# 01-Microcontroller.net
KiCad netlist of a schematic drawn in Altium Designer
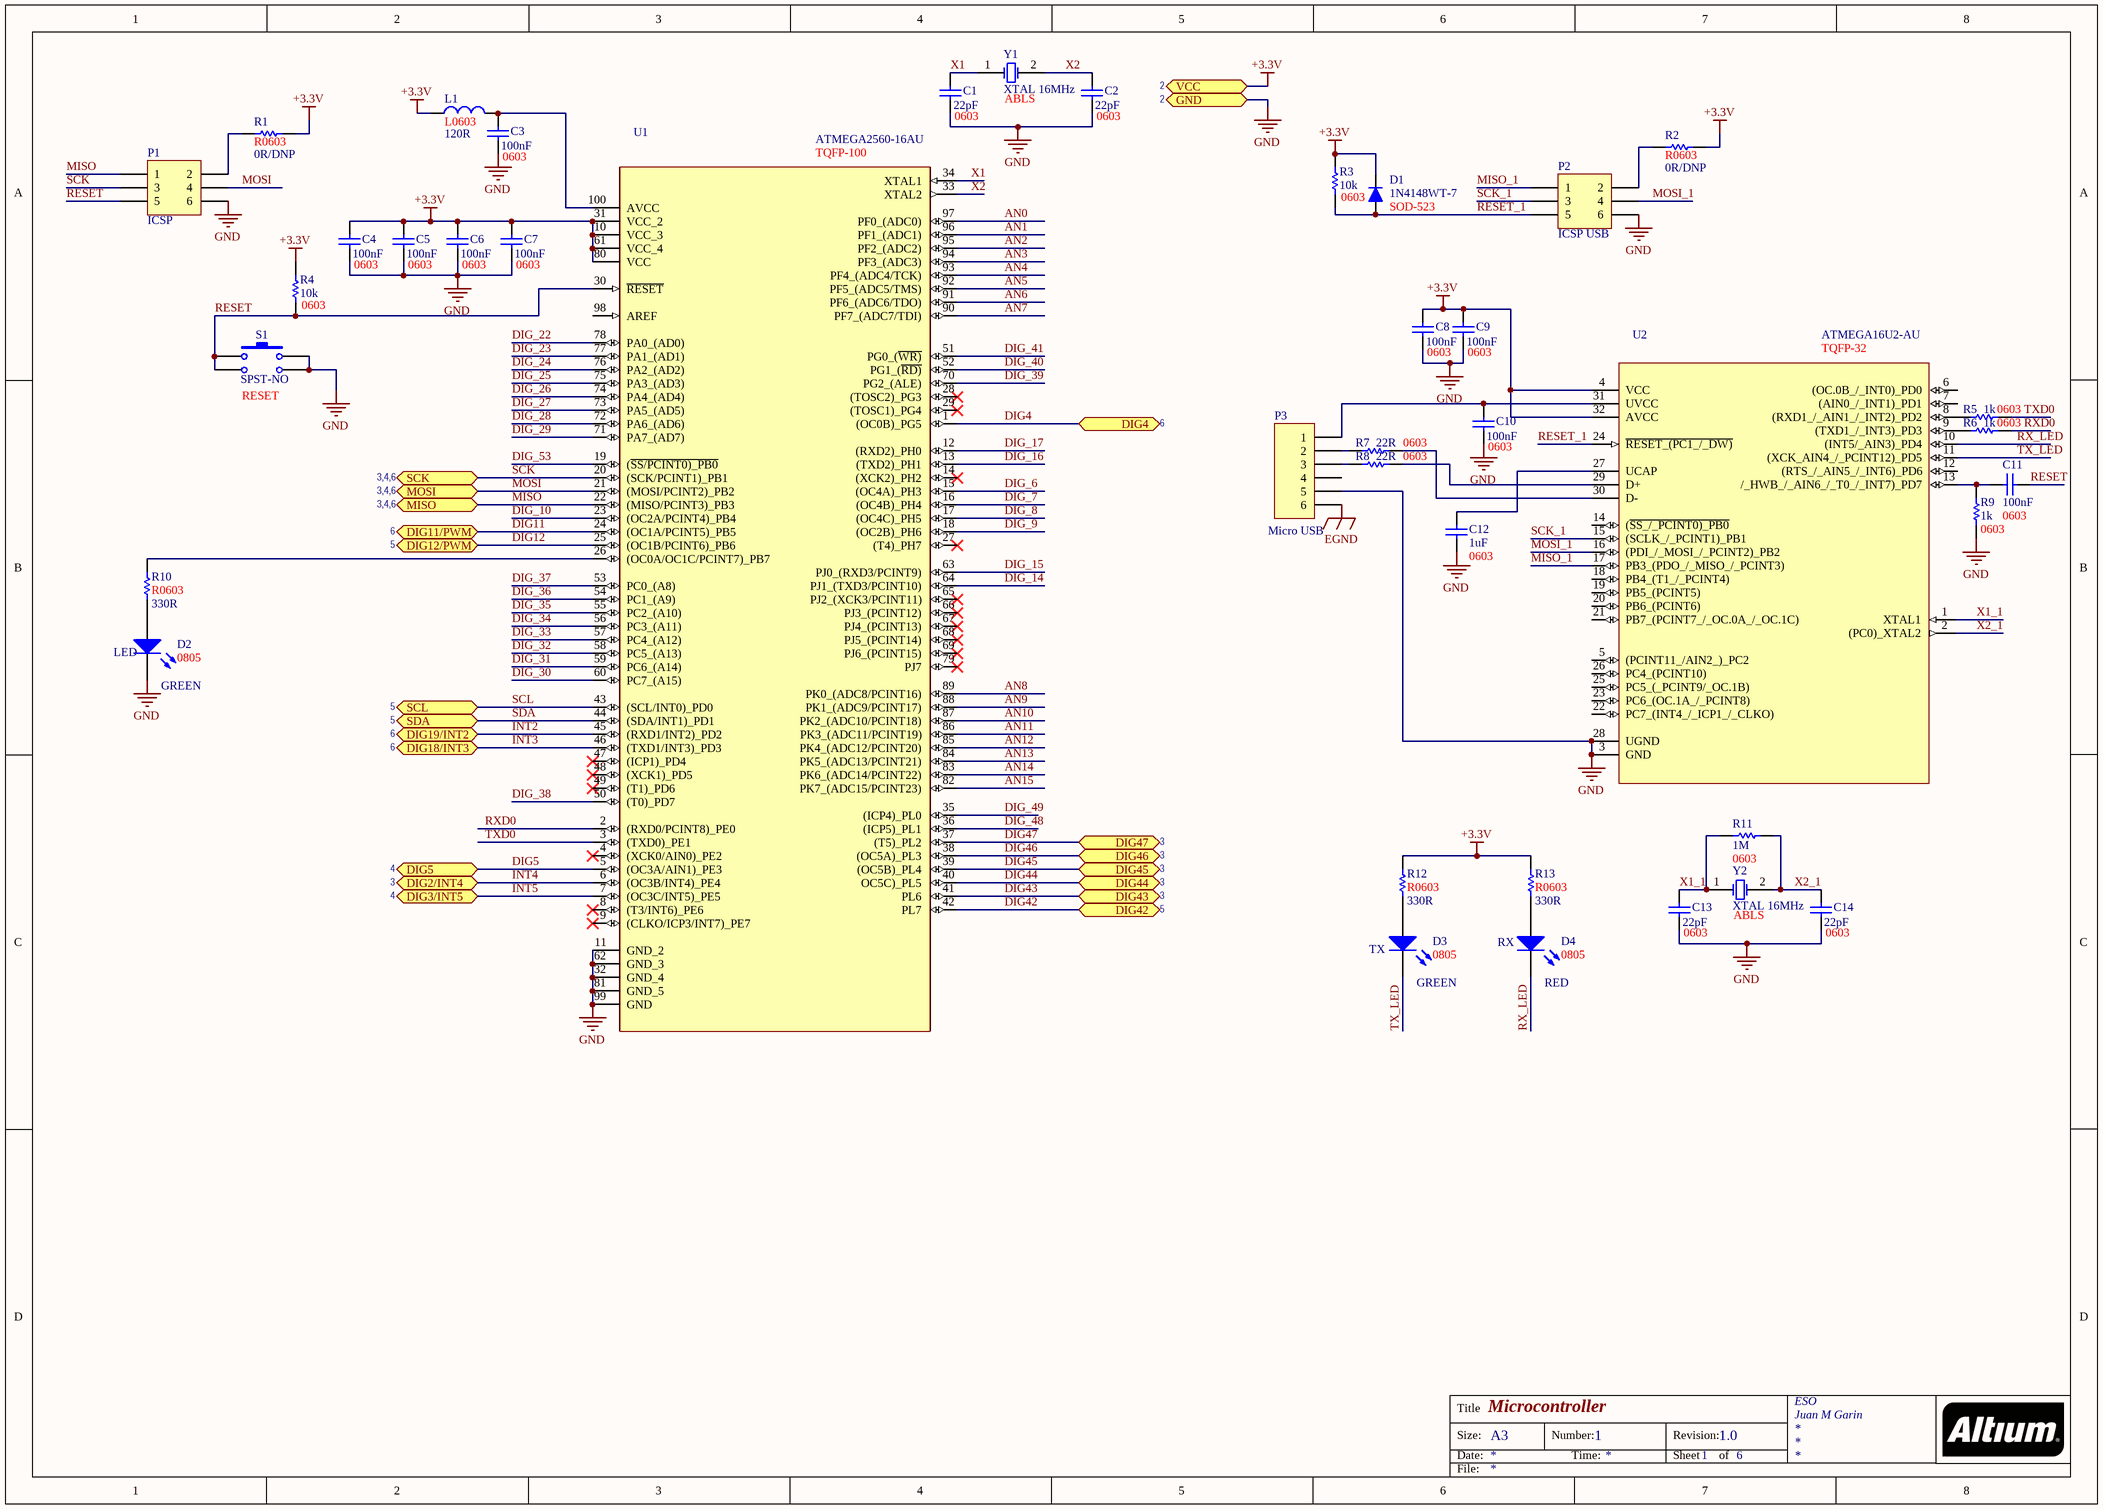
[diagram p0: 01-Microcontroller.SchDoc]

(export (version "E")
  (design (tool "Eeschema 10.0.6"))
  (components
    (comp (ref "C1")
      (value "22pF")
      (footprint "C0603")
      (description "Capacitor (Semiconductor SIM Model)")
      (fields
        (field (name "MANUFACTURER PART NUMBER") "885012006004")
        (field (name "PACKAGEREFERENCE") "0603")
      )
      (libsource (lib "Miscellaneous Devices") (part "Cap Semi"))
    )
    (comp (ref "C2")
      (value "22pF")
      (footprint "C0603")
      (description "Capacitor (Semiconductor SIM Model)")
      (fields
        (field (name "MANUFACTURER PART NUMBER") "885012006004")
        (field (name "PACKAGEREFERENCE") "0603")
      )
      (libsource (lib "Miscellaneous Devices") (part "Cap Semi"))
    )
    (comp (ref "C3")
      (value "100nF")
      (footprint "C0603")
      (description "Capacitor (Semiconductor SIM Model)")
      (fields
        (field (name "MANUFACTURER PART NUMBER") "CL10F104ZO8NNNC")
        (field (name "PACKAGEREFERENCE") "0603")
      )
      (libsource (lib "Miscellaneous Devices") (part "Cap Semi"))
    )
    (comp (ref "C4")
      (value "100nF")
      (footprint "C0603")
      (description "Capacitor (Semiconductor SIM Model)")
      (fields
        (field (name "MANUFACTURER PART NUMBER") "CL10F104ZO8NNNC")
        (field (name "PACKAGEREFERENCE") "0603")
      )
      (libsource (lib "Miscellaneous Devices") (part "Cap Semi"))
    )
    (comp (ref "C5")
      (value "100nF")
      (footprint "C0603")
      (description "Capacitor (Semiconductor SIM Model)")
      (fields
        (field (name "MANUFACTURER PART NUMBER") "CL10F104ZO8NNNC")
        (field (name "PACKAGEREFERENCE") "0603")
      )
      (libsource (lib "Miscellaneous Devices") (part "Cap Semi"))
    )
    (comp (ref "C6")
      (value "100nF")
      (footprint "C0603")
      (description "Capacitor (Semiconductor SIM Model)")
      (fields
        (field (name "MANUFACTURER PART NUMBER") "CL10F104ZO8NNNC")
        (field (name "PACKAGEREFERENCE") "0603")
      )
      (libsource (lib "Miscellaneous Devices") (part "Cap Semi"))
    )
    (comp (ref "C7")
      (value "100nF")
      (footprint "C0603")
      (description "Capacitor (Semiconductor SIM Model)")
      (fields
        (field (name "MANUFACTURER PART NUMBER") "CL10F104ZO8NNNC")
        (field (name "PACKAGEREFERENCE") "0603")
      )
      (libsource (lib "Miscellaneous Devices") (part "Cap Semi"))
    )
    (comp (ref "C8")
      (value "100nF")
      (footprint "C0603")
      (description "Capacitor (Semiconductor SIM Model)")
      (fields
        (field (name "MANUFACTURER PART NUMBER") "CL10F104ZO8NNNC")
        (field (name "PACKAGEREFERENCE") "0603")
      )
      (libsource (lib "Miscellaneous Devices") (part "Cap Semi"))
    )
    (comp (ref "C9")
      (value "100nF")
      (footprint "C0603")
      (description "Capacitor (Semiconductor SIM Model)")
      (fields
        (field (name "MANUFACTURER PART NUMBER") "CL10F104ZO8NNNC")
        (field (name "PACKAGEREFERENCE") "0603")
      )
      (libsource (lib "Miscellaneous Devices") (part "Cap Semi"))
    )
    (comp (ref "C10")
      (value "100nF")
      (footprint "C0603")
      (description "Capacitor (Semiconductor SIM Model)")
      (fields
        (field (name "MANUFACTURER PART NUMBER") "CL10F104ZO8NNNC")
        (field (name "PACKAGEREFERENCE") "0603")
      )
      (libsource (lib "Miscellaneous Devices") (part "Cap Semi"))
    )
    (comp (ref "C11")
      (value "100nF")
      (footprint "C0603")
      (description "Capacitor (Semiconductor SIM Model)")
      (fields
        (field (name "MANUFACTURER PART NUMBER") "CL10F104ZO8NNNC")
        (field (name "PACKAGEREFERENCE") "0603")
      )
      (libsource (lib "Miscellaneous Devices") (part "Cap Semi"))
    )
    (comp (ref "C12")
      (value "1uF")
      (footprint "C0603")
      (description "Capacitor (Semiconductor SIM Model)")
      (fields
        (field (name "MANUFACTURER PART NUMBER") "CL10A105KQ8NNNC")
        (field (name "PACKAGEREFERENCE") "0603")
      )
      (libsource (lib "Miscellaneous Devices") (part "Cap Semi"))
    )
    (comp (ref "C13")
      (value "22pF")
      (footprint "C0603")
      (description "Capacitor (Semiconductor SIM Model)")
      (fields
        (field (name "MANUFACTURER PART NUMBER") "885012006004")
        (field (name "PACKAGEREFERENCE") "0603")
      )
      (libsource (lib "Miscellaneous Devices") (part "Cap Semi"))
    )
    (comp (ref "C14")
      (value "22pF")
      (footprint "C0603")
      (description "Capacitor (Semiconductor SIM Model)")
      (fields
        (field (name "MANUFACTURER PART NUMBER") "885012006004")
        (field (name "PACKAGEREFERENCE") "0603")
      )
      (libsource (lib "Miscellaneous Devices") (part "Cap Semi"))
    )
    (comp (ref "D1")
      (value "1N4148WT-7")
      (footprint "SOD523")
      (description "Diode")
      (fields (field (name "PACKAGEREFERENCE") "SOD-523"))
      (libsource (lib "schematic_library") (part "DIODE"))
    )
    (comp (ref "D2")
      (value "LED")
      (footprint "LED0805")
      (description "GREEN")
      (fields
        (field (name "PACKAGEREFERENCE") "0805")
        (field (name "ALTIUM_VALUE") "GREEN")
        (field (name "MANUFACTURER PART NUMBER") "LTST-S220GKT")
      )
      (libsource (lib "Library_Scott") (part "LED_SMD"))
    )
    (comp (ref "D3")
      (value "TX")
      (footprint "LED0805")
      (description "GREEN")
      (fields
        (field (name "PACKAGEREFERENCE") "0805")
        (field (name "ALTIUM_VALUE") "GREEN")
        (field (name "MANUFACTURER PART NUMBER") "LTST-S220GKT")
      )
      (libsource (lib "Library_Scott") (part "LED_SMD"))
    )
    (comp (ref "D4")
      (value "RX")
      (footprint "LED0805")
      (description "YLW")
      (fields
        (field (name "PACKAGEREFERENCE") "0805")
        (field (name "ALTIUM_VALUE") "RED")
        (field (name "MANUFACTURER PART NUMBER") "LTST-C171KRKT")
      )
      (libsource (lib "Library_Scott") (part "LED_SMD"))
    )
    (comp (ref "L1")
      (value "120R")
      (footprint "L0603")
      (description "Inductor")
      (fields
        (field (name "MANUFACTURER PART NUMBER") "BLM18PG121SN1D")
        (field (name "PACKAGEREFERENCE") "L0603")
      )
      (libsource (lib "schematic_library") (part "Inductor_0603"))
    )
    (comp (ref "P1")
      (value "ICSP")
      (footprint "HDR2X3")
      (description "Header, 3-Pin, Dual row")
      (fields (field (name "MANUFACTURER PART NUMBER") "5-146254-3"))
      (libsource (lib "Library_Scott") (part "Header 3X2"))
    )
    (comp (ref "P2")
      (value "ICSP USB")
      (footprint "HDR2X3")
      (description "Header, 3-Pin, Dual row")
      (fields (field (name "MANUFACTURER PART NUMBER") "5-146254-3"))
      (libsource (lib "Library_Scott") (part "Header 3X2"))
    )
    (comp (ref "P3")
      (value "Micro USB")
      (footprint "CON_MOLEX_105133-0011")
      (description "CONN MICRO USB B 2.0 VERT SMT")
      (fields (field (name "MANUFACTURER PART NUMBER") "1051330011"))
      (libsource (lib "Miscellaneous Connectors") (part "Header 6"))
    )
    (comp (ref "R1")
      (value "0R/DNP")
      (footprint "R0603")
      (description "Resistor")
      (fields
        (field (name "MANUFACTURER PART NUMBER") "CR0603-J/-000ELF")
        (field (name "PACKAGEREFERENCE") "R0603")
      )
      (libsource (lib "schematic_library") (part "Res_0402"))
    )
    (comp (ref "R2")
      (value "0R/DNP")
      (footprint "R0603")
      (description "Resistor")
      (fields
        (field (name "MANUFACTURER PART NUMBER") "CR0603-J/-000ELF")
        (field (name "PACKAGEREFERENCE") "R0603")
      )
      (libsource (lib "schematic_library") (part "Res_0402"))
    )
    (comp (ref "R3")
      (value "10k")
      (footprint "R0603")
      (description "Resistor")
      (fields
        (field (name "MANUFACTURER PART NUMBER") "RMCF0603FT10K0")
        (field (name "PACKAGEREFERENCE") "0603")
      )
      (libsource (lib "Miscellaneous Devices") (part "Res1"))
    )
    (comp (ref "R4")
      (value "10k")
      (footprint "R0603")
      (description "Resistor")
      (fields
        (field (name "MANUFACTURER PART NUMBER") "RMCF0603FT10K0")
        (field (name "PACKAGEREFERENCE") "0603")
      )
      (libsource (lib "Miscellaneous Devices") (part "Res1"))
    )
    (comp (ref "R5")
      (value "1k")
      (footprint "R0603")
      (description "Resistor")
      (fields
        (field (name "MANUFACTURER PART NUMBER") "RMCF0603FG1K00")
        (field (name "PACKAGEREFERENCE") "0603")
      )
      (libsource (lib "Miscellaneous Devices") (part "Res1"))
    )
    (comp (ref "R6")
      (value "1k")
      (footprint "R0603")
      (description "Resistor")
      (fields
        (field (name "MANUFACTURER PART NUMBER") "RMCF0603FG1K00")
        (field (name "PACKAGEREFERENCE") "0603")
      )
      (libsource (lib "Miscellaneous Devices") (part "Res1"))
    )
    (comp (ref "R7")
      (value "22R")
      (footprint "R0603")
      (description "Resistor")
      (fields
        (field (name "MANUFACTURER PART NUMBER") "CRGCQ0603J22R")
        (field (name "PACKAGEREFERENCE") "0603")
      )
      (libsource (lib "Miscellaneous Devices") (part "Res1"))
    )
    (comp (ref "R8")
      (value "22R")
      (footprint "R0603")
      (description "Resistor")
      (fields
        (field (name "MANUFACTURER PART NUMBER") "CRGCQ0603J22R")
        (field (name "PACKAGEREFERENCE") "0603")
      )
      (libsource (lib "Miscellaneous Devices") (part "Res1"))
    )
    (comp (ref "R9")
      (value "1k")
      (footprint "R0603")
      (description "Resistor")
      (fields
        (field (name "MANUFACTURER PART NUMBER") "RMCF0603FG1K00")
        (field (name "PACKAGEREFERENCE") "0603")
      )
      (libsource (lib "Miscellaneous Devices") (part "Res1"))
    )
    (comp (ref "R10")
      (value "330R")
      (footprint "R0603")
      (description "Resistor")
      (fields
        (field (name "MANUFACTURER PART NUMBER") "RMCF0603JT330R")
        (field (name "PACKAGEREFERENCE") "R0603")
      )
      (libsource (lib "schematic_library") (part "Res_0402"))
    )
    (comp (ref "R11")
      (value "1M")
      (footprint "R0603")
      (description "Resistor")
      (fields
        (field (name "MANUFACTURER PART NUMBER") "RMCF0603FG1M00")
        (field (name "PACKAGEREFERENCE") "0603")
      )
      (libsource (lib "Miscellaneous Devices") (part "Res1"))
    )
    (comp (ref "R12")
      (value "330R")
      (footprint "R0603")
      (description "Resistor")
      (fields
        (field (name "MANUFACTURER PART NUMBER") "RMCF0603JT330R")
        (field (name "PACKAGEREFERENCE") "R0603")
      )
      (libsource (lib "schematic_library") (part "Res_0402"))
    )
    (comp (ref "R13")
      (value "330R")
      (footprint "R0603")
      (description "Resistor")
      (fields
        (field (name "MANUFACTURER PART NUMBER") "RMCF0603JT330R")
        (field (name "PACKAGEREFERENCE") "R0603")
      )
      (libsource (lib "schematic_library") (part "Res_0402"))
    )
    (comp (ref "S1")
      (value "SPST-NO")
      (footprint "DPST-4")
      (description "Switch")
      (fields
        (field (name "MANUFACTURER PART NUMBER") "PTS645SM43SMTR92 LFS")
        (field (name "FUNCTION") "RESET")
      )
      (libsource (lib "Library_Scott") (part "SW-PB"))
    )
    (comp (ref "U1")
      (value "ATMEGA2560-16AU")
      (footprint "TQFP100")
      (fields (field (name "PACKAGEREFERENCE") "TQFP-100"))
      (libsource (lib "Library") (part "ATMEGA2560-16AU"))
    )
    (comp (ref "U2")
      (value "ATMEGA16U2-AU")
      (footprint "32A_N")
      (description "MCU 8-bit ATmega AVR RISC 16KB Flash 3.3V/5V 32-Pin TQFP")
      (fields (field (name "PACKAGE") "TQFP-32"))
      (libsource (lib "Library") (part "ATMEGA16U2-AU"))
    )
    (comp (ref "Y1")
      (value "XTAL 16MHz")
      (footprint "XTAL-SMD")
      (description "Crystal Oscillator 16MHz SMD")
      (fields
        (field (name "MANUFACTURER PART NUMBER") "ABLS-16.000MHZ-B2-T")
        (field (name "PACKAGEREFERENCE") "ABLS")
      )
      (libsource (lib "Library_Scott") (part "XTAL 16MHz"))
    )
    (comp (ref "Y2")
      (value "XTAL 16MHz")
      (footprint "XTAL-SMD")
      (description "Crystal Oscillator 16MHz SMD")
      (fields
        (field (name "MANUFACTURER PART NUMBER") "ABLS-16.000MHZ-B2-T")
        (field (name "PACKAGEREFERENCE") "ABLS")
      )
      (libsource (lib "Library_Scott") (part "XTAL 16MHz"))
    )
  )
  (nets
    (net (code "1") (name "+3.3V") (class "Default")
      (node (ref "C4") (pin "2") (pinfunction "2_2") (pintype "passive"))
      (node (ref "C5") (pin "2") (pinfunction "2_2") (pintype "passive"))
      (node (ref "C6") (pin "2") (pinfunction "2_2") (pintype "passive"))
      (node (ref "C7") (pin "2") (pinfunction "2_2") (pintype "passive"))
      (node (ref "C8") (pin "2") (pinfunction "2_2") (pintype "passive"))
      (node (ref "C9") (pin "2") (pinfunction "2_2") (pintype "passive"))
      (node (ref "D1") (pin "2") (pinfunction "K_2") (pintype "passive"))
      (node (ref "L1") (pin "1") (pinfunction "1_1") (pintype "passive"))
      (node (ref "R1") (pin "2") (pinfunction "2_2") (pintype "passive"))
      (node (ref "R12") (pin "2") (pinfunction "2_2") (pintype "passive"))
      (node (ref "R13") (pin "2") (pinfunction "2_2") (pintype "passive"))
      (node (ref "R2") (pin "2") (pinfunction "2_2") (pintype "passive"))
      (node (ref "R3") (pin "1") (pinfunction "1_1") (pintype "passive"))
      (node (ref "R4") (pin "1") (pinfunction "1_1") (pintype "passive"))
      (node (ref "U1") (pin "10") (pinfunction "VCC_3_10") (pintype "power_in"))
      (node (ref "U1") (pin "31") (pinfunction "VCC_2_31") (pintype "power_in"))
      (node (ref "U1") (pin "61") (pinfunction "VCC_4_61") (pintype "power_in"))
      (node (ref "U1") (pin "80") (pinfunction "VCC_80") (pintype "power_in"))
      (node (ref "U2") (pin "32") (pinfunction "AVCC_32") (pintype "power_in"))
      (node (ref "U2") (pin "4") (pinfunction "VCC_4") (pintype "power_in"))
    )
    (net (code "2") (name "/AN0") (class "Default")
      (node (ref "U1") (pin "97") (pinfunction "PF0_(ADC0)_97") (pintype "bidirectional"))
    )
    (net (code "3") (name "/AN1") (class "Default")
      (node (ref "U1") (pin "96") (pinfunction "PF1_(ADC1)_96") (pintype "bidirectional"))
    )
    (net (code "4") (name "/AN2") (class "Default")
      (node (ref "U1") (pin "95") (pinfunction "PF2_(ADC2)_95") (pintype "bidirectional"))
    )
    (net (code "5") (name "/AN3") (class "Default")
      (node (ref "U1") (pin "94") (pinfunction "PF3_(ADC3)_94") (pintype "bidirectional"))
    )
    (net (code "6") (name "/AN4") (class "Default")
      (node (ref "U1") (pin "93") (pinfunction "PF4_(ADC4/TCK)_93") (pintype "bidirectional"))
    )
    (net (code "7") (name "/AN5") (class "Default")
      (node (ref "U1") (pin "92") (pinfunction "PF5_(ADC5/TMS)_92") (pintype "bidirectional"))
    )
    (net (code "8") (name "/AN6") (class "Default")
      (node (ref "U1") (pin "91") (pinfunction "PF6_(ADC6/TDO)_91") (pintype "bidirectional"))
    )
    (net (code "9") (name "/AN7") (class "Default")
      (node (ref "U1") (pin "90") (pinfunction "PF7_(ADC7/TDI)_90") (pintype "bidirectional"))
    )
    (net (code "10") (name "/AN8") (class "Default")
      (node (ref "U1") (pin "89") (pinfunction "PK0_(ADC8/PCINT16)_89") (pintype "bidirectional"))
    )
    (net (code "11") (name "/AN9") (class "Default")
      (node (ref "U1") (pin "88") (pinfunction "PK1_(ADC9/PCINT17)_88") (pintype "bidirectional"))
    )
    (net (code "12") (name "/AN10") (class "Default")
      (node (ref "U1") (pin "87") (pinfunction "PK2_(ADC10/PCINT18)_87") (pintype "bidirectional"))
    )
    (net (code "13") (name "/AN11") (class "Default")
      (node (ref "U1") (pin "86") (pinfunction "PK3_(ADC11/PCINT19)_86") (pintype "bidirectional"))
    )
    (net (code "14") (name "/AN12") (class "Default")
      (node (ref "U1") (pin "85") (pinfunction "PK4_(ADC12/PCINT20)_85") (pintype "bidirectional"))
    )
    (net (code "15") (name "/AN13") (class "Default")
      (node (ref "U1") (pin "84") (pinfunction "PK5_(ADC13/PCINT21)_84") (pintype "bidirectional"))
    )
    (net (code "16") (name "/AN14") (class "Default")
      (node (ref "U1") (pin "83") (pinfunction "PK6_(ADC14/PCINT22)_83") (pintype "bidirectional"))
    )
    (net (code "17") (name "/AN15") (class "Default")
      (node (ref "U1") (pin "82") (pinfunction "PK7_(ADC15/PCINT23)_82") (pintype "bidirectional"))
    )
    (net (code "18") (name "/DIG4") (class "Default")
      (node (ref "U1") (pin "1") (pinfunction "(OC0B)_PG5_1") (pintype "bidirectional"))
    )
    (net (code "19") (name "/DIG5") (class "Default")
      (node (ref "U1") (pin "5") (pinfunction "(OC3A/AIN1)_PE3_5") (pintype "bidirectional"))
    )
    (net (code "20") (name "/DIG11") (class "Default")
      (node (ref "U1") (pin "24") (pinfunction "(OC1A/PCINT5)_PB5_24") (pintype "bidirectional"))
    )
    (net (code "21") (name "/DIG12") (class "Default")
      (node (ref "U1") (pin "25") (pinfunction "(OC1B/PCINT6)_PB6_25") (pintype "bidirectional"))
    )
    (net (code "22") (name "/DIG42") (class "Default")
      (node (ref "U1") (pin "42") (pinfunction "PL7_42") (pintype "bidirectional"))
    )
    (net (code "23") (name "/DIG43") (class "Default")
      (node (ref "U1") (pin "41") (pinfunction "PL6_41") (pintype "bidirectional"))
    )
    (net (code "24") (name "/DIG44") (class "Default")
      (node (ref "U1") (pin "40") (pinfunction "OC5C)_PL5_40") (pintype "bidirectional"))
    )
    (net (code "25") (name "/DIG45") (class "Default")
      (node (ref "U1") (pin "39") (pinfunction "(OC5B)_PL4_39") (pintype "bidirectional"))
    )
    (net (code "26") (name "/DIG46") (class "Default")
      (node (ref "U1") (pin "38") (pinfunction "(OC5A)_PL3_38") (pintype "bidirectional"))
    )
    (net (code "27") (name "/DIG47") (class "Default")
      (node (ref "U1") (pin "37") (pinfunction "(T5)_PL2_37") (pintype "bidirectional"))
    )
    (net (code "28") (name "/DIG_6") (class "Default")
      (node (ref "U1") (pin "15") (pinfunction "(OC4A)_PH3_15") (pintype "bidirectional"))
    )
    (net (code "29") (name "/DIG_7") (class "Default")
      (node (ref "U1") (pin "16") (pinfunction "(OC4B)_PH4_16") (pintype "bidirectional"))
    )
    (net (code "30") (name "/DIG_8") (class "Default")
      (node (ref "U1") (pin "17") (pinfunction "(OC4C)_PH5_17") (pintype "bidirectional"))
    )
    (net (code "31") (name "/DIG_9") (class "Default")
      (node (ref "U1") (pin "18") (pinfunction "(OC2B)_PH6_18") (pintype "bidirectional"))
    )
    (net (code "32") (name "/DIG_10") (class "Default")
      (node (ref "U1") (pin "23") (pinfunction "(OC2A/PCINT4)_PB4_23") (pintype "bidirectional"))
    )
    (net (code "33") (name "/DIG_14") (class "Default")
      (node (ref "U1") (pin "64") (pinfunction "PJ1_(TXD3/PCINT10)_64") (pintype "bidirectional"))
    )
    (net (code "34") (name "/DIG_15") (class "Default")
      (node (ref "U1") (pin "63") (pinfunction "PJ0_(RXD3/PCINT9)_63") (pintype "bidirectional"))
    )
    (net (code "35") (name "/DIG_16") (class "Default")
      (node (ref "U1") (pin "13") (pinfunction "(TXD2)_PH1_13") (pintype "bidirectional"))
    )
    (net (code "36") (name "/DIG_17") (class "Default")
      (node (ref "U1") (pin "12") (pinfunction "(RXD2)_PH0_12") (pintype "bidirectional"))
    )
    (net (code "37") (name "/DIG_22") (class "Default")
      (node (ref "U1") (pin "78") (pinfunction "PA0_(AD0)_78") (pintype "bidirectional"))
    )
    (net (code "38") (name "/DIG_23") (class "Default")
      (node (ref "U1") (pin "77") (pinfunction "PA1_(AD1)_77") (pintype "bidirectional"))
    )
    (net (code "39") (name "/DIG_24") (class "Default")
      (node (ref "U1") (pin "76") (pinfunction "PA2_(AD2)_76") (pintype "bidirectional"))
    )
    (net (code "40") (name "/DIG_25") (class "Default")
      (node (ref "U1") (pin "75") (pinfunction "PA3_(AD3)_75") (pintype "bidirectional"))
    )
    (net (code "41") (name "/DIG_26") (class "Default")
      (node (ref "U1") (pin "74") (pinfunction "PA4_(AD4)_74") (pintype "bidirectional"))
    )
    (net (code "42") (name "/DIG_27") (class "Default")
      (node (ref "U1") (pin "73") (pinfunction "PA5_(AD5)_73") (pintype "bidirectional"))
    )
    (net (code "43") (name "/DIG_28") (class "Default")
      (node (ref "U1") (pin "72") (pinfunction "PA6_(AD6)_72") (pintype "bidirectional"))
    )
    (net (code "44") (name "/DIG_29") (class "Default")
      (node (ref "U1") (pin "71") (pinfunction "PA7_(AD7)_71") (pintype "bidirectional"))
    )
    (net (code "45") (name "/DIG_30") (class "Default")
      (node (ref "U1") (pin "60") (pinfunction "PC7_(A15)_60") (pintype "bidirectional"))
    )
    (net (code "46") (name "/DIG_31") (class "Default")
      (node (ref "U1") (pin "59") (pinfunction "PC6_(A14)_59") (pintype "bidirectional"))
    )
    (net (code "47") (name "/DIG_32") (class "Default")
      (node (ref "U1") (pin "58") (pinfunction "PC5_(A13)_58") (pintype "bidirectional"))
    )
    (net (code "48") (name "/DIG_33") (class "Default")
      (node (ref "U1") (pin "57") (pinfunction "PC4_(A12)_57") (pintype "bidirectional"))
    )
    (net (code "49") (name "/DIG_34") (class "Default")
      (node (ref "U1") (pin "56") (pinfunction "PC3_(A11)_56") (pintype "bidirectional"))
    )
    (net (code "50") (name "/DIG_35") (class "Default")
      (node (ref "U1") (pin "55") (pinfunction "PC2_(A10)_55") (pintype "bidirectional"))
    )
    (net (code "51") (name "/DIG_36") (class "Default")
      (node (ref "U1") (pin "54") (pinfunction "PC1_(A9)_54") (pintype "bidirectional"))
    )
    (net (code "52") (name "/DIG_37") (class "Default")
      (node (ref "U1") (pin "53") (pinfunction "PC0_(A8)_53") (pintype "bidirectional"))
    )
    (net (code "53") (name "/DIG_38") (class "Default")
      (node (ref "U1") (pin "50") (pinfunction "(T0)_PD7_50") (pintype "bidirectional"))
    )
    (net (code "54") (name "/DIG_39") (class "Default")
      (node (ref "U1") (pin "70") (pinfunction "PG2_(ALE)_70") (pintype "bidirectional"))
    )
    (net (code "55") (name "/DIG_40") (class "Default")
      (node (ref "U1") (pin "52") (pinfunction "PG1_(~{RD)}_52") (pintype "bidirectional"))
    )
    (net (code "56") (name "/DIG_41") (class "Default")
      (node (ref "U1") (pin "51") (pinfunction "PG0_(~{WR)}_51") (pintype "bidirectional"))
    )
    (net (code "57") (name "/DIG_48") (class "Default")
      (node (ref "U1") (pin "36") (pinfunction "(ICP5)_PL1_36") (pintype "bidirectional"))
    )
    (net (code "58") (name "/DIG_49") (class "Default")
      (node (ref "U1") (pin "35") (pinfunction "(ICP4)_PL0_35") (pintype "bidirectional"))
    )
    (net (code "59") (name "/DIG_53") (class "Default")
      (node (ref "U1") (pin "19") (pinfunction "(~{SS/PCINT0)_PB0}_19") (pintype "bidirectional"))
    )
    (net (code "60") (name "/INT2") (class "Default")
      (node (ref "U1") (pin "45") (pinfunction "(RXD1/INT2)_PD2_45") (pintype "bidirectional"))
    )
    (net (code "61") (name "/INT3") (class "Default")
      (node (ref "U1") (pin "46") (pinfunction "(TXD1/INT3)_PD3_46") (pintype "bidirectional"))
    )
    (net (code "62") (name "/INT4") (class "Default")
      (node (ref "U1") (pin "6") (pinfunction "(OC3B/INT4)_PE4_6") (pintype "bidirectional"))
    )
    (net (code "63") (name "/INT5") (class "Default")
      (node (ref "U1") (pin "7") (pinfunction "(OC3C/INT5)_PE5_7") (pintype "bidirectional"))
    )
    (net (code "64") (name "/MISO") (class "Default")
      (node (ref "P1") (pin "1") (pinfunction "1_1") (pintype "passive"))
      (node (ref "U1") (pin "22") (pinfunction "(MISO/PCINT3)_PB3_22") (pintype "bidirectional"))
    )
    (net (code "65") (name "/MISO_1") (class "Default")
      (node (ref "P2") (pin "1") (pinfunction "1_1") (pintype "passive"))
      (node (ref "U2") (pin "17") (pinfunction "PB3_(PDO_/_MISO_/_PCINT3)_17") (pintype "bidirectional"))
    )
    (net (code "66") (name "/MOSI") (class "Default")
      (node (ref "P1") (pin "4") (pinfunction "4_4") (pintype "passive"))
      (node (ref "U1") (pin "21") (pinfunction "(MOSI/PCINT2)_PB2_21") (pintype "bidirectional"))
    )
    (net (code "67") (name "/MOSI_1") (class "Default")
      (node (ref "P2") (pin "4") (pinfunction "4_4") (pintype "passive"))
      (node (ref "U2") (pin "16") (pinfunction "(PDI_/_MOSI_/_PCINT2)_PB2_16") (pintype "bidirectional"))
    )
    (net (code "68") (name "/RESET") (class "Default")
      (node (ref "C11") (pin "1") (pinfunction "1_1") (pintype "passive"))
      (node (ref "P1") (pin "5") (pinfunction "5_5") (pintype "passive"))
      (node (ref "R4") (pin "2") (pinfunction "2_2") (pintype "passive"))
      (node (ref "S1") (pin "1") (pinfunction "1_1") (pintype "passive"))
      (node (ref "S1") (pin "2") (pinfunction "2_2") (pintype "passive"))
      (node (ref "U1") (pin "30") (pinfunction "~{RESET}_30") (pintype "input"))
    )
    (net (code "69") (name "/RESET_1") (class "Default")
      (node (ref "D1") (pin "1") (pinfunction "A_1") (pintype "passive"))
      (node (ref "P2") (pin "5") (pinfunction "5_5") (pintype "passive"))
      (node (ref "R3") (pin "2") (pinfunction "2_2") (pintype "passive"))
      (node (ref "U2") (pin "24") (pinfunction "~{RESET_(PC1_/_DW)}_24") (pintype "input"))
    )
    (net (code "70") (name "/RXD0") (class "Default")
      (node (ref "R6") (pin "2") (pinfunction "2_2") (pintype "passive"))
      (node (ref "U1") (pin "2") (pinfunction "(RXD0/PCINT8)_PE0_2") (pintype "bidirectional"))
    )
    (net (code "71") (name "/RX_LED") (class "Default")
      (node (ref "D4") (pin "2") (pinfunction "K_2") (pintype "passive"))
      (node (ref "U2") (pin "10") (pinfunction "(INT5/_AIN3)_PD4_10") (pintype "bidirectional"))
    )
    (net (code "72") (name "/SCK") (class "Default")
      (node (ref "P1") (pin "3") (pinfunction "3_3") (pintype "passive"))
      (node (ref "U1") (pin "20") (pinfunction "(SCK/PCINT1)_PB1_20") (pintype "bidirectional"))
    )
    (net (code "73") (name "/SCK_1") (class "Default")
      (node (ref "P2") (pin "3") (pinfunction "3_3") (pintype "passive"))
      (node (ref "U2") (pin "15") (pinfunction "(SCLK_/_PCINT1)_PB1_15") (pintype "bidirectional"))
    )
    (net (code "74") (name "/SCL") (class "Default")
      (node (ref "U1") (pin "43") (pinfunction "(SCL/INT0)_PD0_43") (pintype "bidirectional"))
    )
    (net (code "75") (name "/SDA") (class "Default")
      (node (ref "U1") (pin "44") (pinfunction "(SDA/INT1)_PD1_44") (pintype "bidirectional"))
    )
    (net (code "76") (name "/TXD0") (class "Default")
      (node (ref "R5") (pin "2") (pinfunction "2_2") (pintype "passive"))
      (node (ref "U1") (pin "3") (pinfunction "(TXD0)_PE1_3") (pintype "bidirectional"))
    )
    (net (code "77") (name "/TX_LED") (class "Default")
      (node (ref "D3") (pin "2") (pinfunction "K_2") (pintype "passive"))
      (node (ref "U2") (pin "11") (pinfunction "(XCK_AIN4_/_PCINT12)_PD5_11") (pintype "bidirectional"))
    )
    (net (code "78") (name "/X1") (class "Default")
      (node (ref "C1") (pin "2") (pinfunction "2_2") (pintype "passive"))
      (node (ref "U1") (pin "34") (pinfunction "XTAL1_34") (pintype "input"))
      (node (ref "Y1") (pin "1") (pinfunction "OSC1_1") (pintype "passive"))
    )
    (net (code "79") (name "/X1_1") (class "Default")
      (node (ref "C13") (pin "2") (pinfunction "2_2") (pintype "passive"))
      (node (ref "R11") (pin "2") (pinfunction "2_2") (pintype "passive"))
      (node (ref "U2") (pin "1") (pinfunction "XTAL1_1") (pintype "input"))
      (node (ref "Y2") (pin "1") (pinfunction "OSC1_1") (pintype "passive"))
    )
    (net (code "80") (name "/X2") (class "Default")
      (node (ref "C2") (pin "2") (pinfunction "2_2") (pintype "passive"))
      (node (ref "U1") (pin "33") (pinfunction "XTAL2_33") (pintype "output"))
      (node (ref "Y1") (pin "2") (pinfunction "OSC2_2") (pintype "passive"))
    )
    (net (code "81") (name "/X2_1") (class "Default")
      (node (ref "C14") (pin "2") (pinfunction "2_2") (pintype "passive"))
      (node (ref "R11") (pin "1") (pinfunction "1_1") (pintype "passive"))
      (node (ref "U2") (pin "2") (pinfunction "(PC0)_XTAL2_2") (pintype "output"))
      (node (ref "Y2") (pin "2") (pinfunction "OSC2_2") (pintype "passive"))
    )
    (net (code "82") (name "EGND") (class "Default")
      (node (ref "P3") (pin "6") (pinfunction "6_6") (pintype "passive"))
    )
    (net (code "83") (name "GND") (class "Default")
      (node (ref "C1") (pin "1") (pinfunction "1_1") (pintype "passive"))
      (node (ref "C10") (pin "1") (pinfunction "1_1") (pintype "passive"))
      (node (ref "C12") (pin "2") (pinfunction "2_2") (pintype "passive"))
      (node (ref "C13") (pin "1") (pinfunction "1_1") (pintype "passive"))
      (node (ref "C14") (pin "1") (pinfunction "1_1") (pintype "passive"))
      (node (ref "C2") (pin "1") (pinfunction "1_1") (pintype "passive"))
      (node (ref "C3") (pin "1") (pinfunction "1_1") (pintype "passive"))
      (node (ref "C4") (pin "1") (pinfunction "1_1") (pintype "passive"))
      (node (ref "C5") (pin "1") (pinfunction "1_1") (pintype "passive"))
      (node (ref "C6") (pin "1") (pinfunction "1_1") (pintype "passive"))
      (node (ref "C7") (pin "1") (pinfunction "1_1") (pintype "passive"))
      (node (ref "C8") (pin "1") (pinfunction "1_1") (pintype "passive"))
      (node (ref "C9") (pin "1") (pinfunction "1_1") (pintype "passive"))
      (node (ref "D2") (pin "2") (pinfunction "K_2") (pintype "passive"))
      (node (ref "P1") (pin "6") (pinfunction "6_6") (pintype "passive"))
      (node (ref "P2") (pin "6") (pinfunction "6_6") (pintype "passive"))
      (node (ref "P3") (pin "5") (pinfunction "5_5") (pintype "passive"))
      (node (ref "R9") (pin "1") (pinfunction "1_1") (pintype "passive"))
      (node (ref "S1") (pin "3") (pinfunction "3_3") (pintype "passive"))
      (node (ref "S1") (pin "4") (pinfunction "4_4") (pintype "passive"))
      (node (ref "U1") (pin "11") (pinfunction "GND_2_11") (pintype "passive"))
      (node (ref "U1") (pin "32") (pinfunction "GND_4_32") (pintype "passive"))
      (node (ref "U1") (pin "62") (pinfunction "GND_3_62") (pintype "passive"))
      (node (ref "U1") (pin "81") (pinfunction "GND_5_81") (pintype "passive"))
      (node (ref "U1") (pin "99") (pinfunction "GND_99") (pintype "passive"))
      (node (ref "U2") (pin "28") (pinfunction "UGND_28") (pintype "passive"))
      (node (ref "U2") (pin "3") (pinfunction "GND_3") (pintype "passive"))
    )
    (net (code "84") (name "Net-(D2-A)") (class "Default")
      (node (ref "D2") (pin "1") (pinfunction "A_1") (pintype "passive"))
      (node (ref "R10") (pin "1") (pinfunction "1_1") (pintype "passive"))
    )
    (net (code "85") (name "Net-(D3-A)") (class "Default")
      (node (ref "D3") (pin "1") (pinfunction "A_1") (pintype "passive"))
      (node (ref "R12") (pin "1") (pinfunction "1_1") (pintype "passive"))
    )
    (net (code "86") (name "Net-(D4-A)") (class "Default")
      (node (ref "D4") (pin "1") (pinfunction "A_1") (pintype "passive"))
      (node (ref "R13") (pin "1") (pinfunction "1_1") (pintype "passive"))
    )
    (net (code "87") (name "Net-(P1-Pad2)") (class "Default")
      (node (ref "P1") (pin "2") (pinfunction "2_2") (pintype "passive"))
      (node (ref "R1") (pin "1") (pinfunction "1_1") (pintype "passive"))
    )
    (net (code "88") (name "Net-(P2-Pad2)") (class "Default")
      (node (ref "P2") (pin "2") (pinfunction "2_2") (pintype "passive"))
      (node (ref "R2") (pin "1") (pinfunction "1_1") (pintype "passive"))
    )
    (net (code "89") (name "Net-(P3-Pad2)") (class "Default")
      (node (ref "P3") (pin "2") (pinfunction "2_2") (pintype "passive"))
      (node (ref "R7") (pin "2") (pinfunction "2_2") (pintype "passive"))
    )
    (net (code "90") (name "Net-(P3-Pad3)") (class "Default")
      (node (ref "P3") (pin "3") (pinfunction "3_3") (pintype "passive"))
      (node (ref "R8") (pin "2") (pinfunction "2_2") (pintype "passive"))
    )
    (net (code "91") (name "Net-(U1-(OC0A{slash}OC1C{slash}PCINT7)_PB7)") (class "Default")
      (node (ref "R10") (pin "2") (pinfunction "2_2") (pintype "passive"))
      (node (ref "U1") (pin "26") (pinfunction "(OC0A/OC1C/PCINT7)_PB7_26") (pintype "bidirectional"))
    )
    (net (code "92") (name "Net-(U1-AVCC)") (class "Default")
      (node (ref "C3") (pin "2") (pinfunction "2_2") (pintype "passive"))
      (node (ref "L1") (pin "2") (pinfunction "2_2") (pintype "passive"))
      (node (ref "U1") (pin "100") (pinfunction "AVCC_100") (pintype "power_in"))
    )
    (net (code "93") (name "Net-(U2-(RXD1_{slash}_AIN1_{slash}_INT2)_PD2)") (class "Default")
      (node (ref "R5") (pin "1") (pinfunction "1_1") (pintype "passive"))
      (node (ref "U2") (pin "8") (pinfunction "(RXD1_/_AIN1_/_INT2)_PD2_8") (pintype "bidirectional"))
    )
    (net (code "94") (name "Net-(U2-(TXD1_{slash}_INT3)_PD3)") (class "Default")
      (node (ref "R6") (pin "1") (pinfunction "1_1") (pintype "passive"))
      (node (ref "U2") (pin "9") (pinfunction "(TXD1_/_INT3)_PD3_9") (pintype "bidirectional"))
    )
    (net (code "95") (name "Net-(U2-D+)") (class "Default")
      (node (ref "R8") (pin "1") (pinfunction "1_1") (pintype "passive"))
      (node (ref "U2") (pin "29") (pinfunction "D+_29") (pintype "passive"))
    )
    (net (code "96") (name "Net-(U2-D-)") (class "Default")
      (node (ref "R7") (pin "1") (pinfunction "1_1") (pintype "passive"))
      (node (ref "U2") (pin "30") (pinfunction "D-_30") (pintype "passive"))
    )
    (net (code "97") (name "Net-(U2-UCAP)") (class "Default")
      (node (ref "C12") (pin "1") (pinfunction "1_1") (pintype "passive"))
      (node (ref "U2") (pin "27") (pinfunction "UCAP_27") (pintype "passive"))
    )
    (net (code "98") (name "Net-(U2-UVCC)") (class "Default")
      (node (ref "C10") (pin "2") (pinfunction "2_2") (pintype "passive"))
      (node (ref "P3") (pin "1") (pinfunction "1_1") (pintype "passive"))
      (node (ref "U2") (pin "31") (pinfunction "UVCC_31") (pintype "power_in"))
    )
    (net (code "99") (name "Net-(U2-{slash}_HWB_{slash}_AIN6_{slash}_T0_{slash}_INT7)_PD7)") (class "Default")
      (node (ref "C11") (pin "2") (pinfunction "2_2") (pintype "passive"))
      (node (ref "R9") (pin "2") (pinfunction "2_2") (pintype "passive"))
      (node (ref "U2") (pin "13") (pinfunction "/_HWB_/_AIN6_/_T0_/_INT7)_PD7_13") (pintype "bidirectional"))
    )
    (net (code "100") (name "unconnected-(P3-Pad4)") (class "Default")
      (node (ref "P3") (pin "4") (pinfunction "4_4") (pintype "passive"))
    )
    (net (code "101") (name "unconnected-(U1-(CLKO{slash}ICP3{slash}INT7)_PE7-Pad9)") (class "Default")
      (node (ref "U1") (pin "9") (pinfunction "(CLKO/ICP3/INT7)_PE7_9") (pintype "bidirectional+no_connect"))
    )
    (net (code "102") (name "unconnected-(U1-(ICP1)_PD4-Pad47)") (class "Default")
      (node (ref "U1") (pin "47") (pinfunction "(ICP1)_PD4_47") (pintype "bidirectional+no_connect"))
    )
    (net (code "103") (name "unconnected-(U1-(T1)_PD6-Pad49)") (class "Default")
      (node (ref "U1") (pin "49") (pinfunction "(T1)_PD6_49") (pintype "bidirectional+no_connect"))
    )
    (net (code "104") (name "unconnected-(U1-(T3{slash}INT6)_PE6-Pad8)") (class "Default")
      (node (ref "U1") (pin "8") (pinfunction "(T3/INT6)_PE6_8") (pintype "bidirectional+no_connect"))
    )
    (net (code "105") (name "unconnected-(U1-(T4)_PH7-Pad27)") (class "Default")
      (node (ref "U1") (pin "27") (pinfunction "(T4)_PH7_27") (pintype "bidirectional+no_connect"))
    )
    (net (code "106") (name "unconnected-(U1-(TOSC1)_PG4-Pad29)") (class "Default")
      (node (ref "U1") (pin "29") (pinfunction "(TOSC1)_PG4_29") (pintype "bidirectional+no_connect"))
    )
    (net (code "107") (name "unconnected-(U1-(TOSC2)_PG3-Pad28)") (class "Default")
      (node (ref "U1") (pin "28") (pinfunction "(TOSC2)_PG3_28") (pintype "bidirectional+no_connect"))
    )
    (net (code "108") (name "unconnected-(U1-(XCK0{slash}AIN0)_PE2-Pad4)") (class "Default")
      (node (ref "U1") (pin "4") (pinfunction "(XCK0/AIN0)_PE2_4") (pintype "bidirectional+no_connect"))
    )
    (net (code "109") (name "unconnected-(U1-(XCK1)_PD5-Pad48)") (class "Default")
      (node (ref "U1") (pin "48") (pinfunction "(XCK1)_PD5_48") (pintype "bidirectional+no_connect"))
    )
    (net (code "110") (name "unconnected-(U1-(XCK2)_PH2-Pad14)") (class "Default")
      (node (ref "U1") (pin "14") (pinfunction "(XCK2)_PH2_14") (pintype "bidirectional+no_connect"))
    )
    (net (code "111") (name "unconnected-(U1-AREF-Pad98)") (class "Default")
      (node (ref "U1") (pin "98") (pinfunction "AREF_98") (pintype "input"))
    )
    (net (code "112") (name "unconnected-(U1-PJ2_(XCK3{slash}PCINT11)-Pad65)") (class "Default")
      (node (ref "U1") (pin "65") (pinfunction "PJ2_(XCK3/PCINT11)_65") (pintype "bidirectional+no_connect"))
    )
    (net (code "113") (name "unconnected-(U1-PJ3_(PCINT12)-Pad66)") (class "Default")
      (node (ref "U1") (pin "66") (pinfunction "PJ3_(PCINT12)_66") (pintype "bidirectional+no_connect"))
    )
    (net (code "114") (name "unconnected-(U1-PJ4_(PCINT13)-Pad67)") (class "Default")
      (node (ref "U1") (pin "67") (pinfunction "PJ4_(PCINT13)_67") (pintype "bidirectional+no_connect"))
    )
    (net (code "115") (name "unconnected-(U1-PJ5_(PCINT14)-Pad68)") (class "Default")
      (node (ref "U1") (pin "68") (pinfunction "PJ5_(PCINT14)_68") (pintype "bidirectional+no_connect"))
    )
    (net (code "116") (name "unconnected-(U1-PJ6_(PCINT15)-Pad69)") (class "Default")
      (node (ref "U1") (pin "69") (pinfunction "PJ6_(PCINT15)_69") (pintype "bidirectional+no_connect"))
    )
    (net (code "117") (name "unconnected-(U1-PJ7-Pad79)") (class "Default")
      (node (ref "U1") (pin "79") (pinfunction "PJ7_79") (pintype "bidirectional+no_connect"))
    )
    (net (code "118") (name "unconnected-(U2-(AIN0_{slash}_INT1)_PD1-Pad7)") (class "Default")
      (node (ref "U2") (pin "7") (pinfunction "(AIN0_/_INT1)_PD1_7") (pintype "bidirectional"))
    )
    (net (code "119") (name "unconnected-(U2-(OC.0B_{slash}_INT0)_PD0-Pad6)") (class "Default")
      (node (ref "U2") (pin "6") (pinfunction "(OC.0B_/_INT0)_PD0_6") (pintype "bidirectional"))
    )
    (net (code "120") (name "unconnected-(U2-(PCINT11_{slash}AIN2_)_PC2-Pad5)") (class "Default")
      (node (ref "U2") (pin "5") (pinfunction "(PCINT11_/AIN2_)_PC2_5") (pintype "bidirectional"))
    )
    (net (code "121") (name "unconnected-(U2-(RTS_{slash}_AIN5_{slash}_INT6)_PD6-Pad12)") (class "Default")
      (node (ref "U2") (pin "12") (pinfunction "(RTS_/_AIN5_/_INT6)_PD6_12") (pintype "bidirectional"))
    )
    (net (code "122") (name "unconnected-(U2-(~{SS_{slash}_PCINT0)_PB0}-Pad14)") (class "Default")
      (node (ref "U2") (pin "14") (pinfunction "(~{SS_/_PCINT0)_PB0}_14") (pintype "bidirectional"))
    )
    (net (code "123") (name "unconnected-(U2-PB4_(T1_{slash}_PCINT4)-Pad18)") (class "Default")
      (node (ref "U2") (pin "18") (pinfunction "PB4_(T1_/_PCINT4)_18") (pintype "bidirectional"))
    )
    (net (code "124") (name "unconnected-(U2-PB5_(PCINT5)-Pad19)") (class "Default")
      (node (ref "U2") (pin "19") (pinfunction "PB5_(PCINT5)_19") (pintype "bidirectional"))
    )
    (net (code "125") (name "unconnected-(U2-PB6_(PCINT6)-Pad20)") (class "Default")
      (node (ref "U2") (pin "20") (pinfunction "PB6_(PCINT6)_20") (pintype "bidirectional"))
    )
    (net (code "126") (name "unconnected-(U2-PB7_(PCINT7_{slash}_OC.0A_{slash}_OC.1C)-Pad21)") (class "Default")
      (node (ref "U2") (pin "21") (pinfunction "PB7_(PCINT7_/_OC.0A_/_OC.1C)_21") (pintype "bidirectional"))
    )
    (net (code "127") (name "unconnected-(U2-PC4_(PCINT10)-Pad26)") (class "Default")
      (node (ref "U2") (pin "26") (pinfunction "PC4_(PCINT10)_26") (pintype "bidirectional"))
    )
    (net (code "128") (name "unconnected-(U2-PC5_(_PCINT9{slash}_OC.1B)-Pad25)") (class "Default")
      (node (ref "U2") (pin "25") (pinfunction "PC5_(_PCINT9/_OC.1B)_25") (pintype "bidirectional"))
    )
    (net (code "129") (name "unconnected-(U2-PC6_(OC.1A_{slash}_PCINT8)-Pad23)") (class "Default")
      (node (ref "U2") (pin "23") (pinfunction "PC6_(OC.1A_/_PCINT8)_23") (pintype "bidirectional"))
    )
    (net (code "130") (name "unconnected-(U2-PC7_(INT4_{slash}_ICP1_{slash}_CLKO)-Pad22)") (class "Default")
      (node (ref "U2") (pin "22") (pinfunction "PC7_(INT4_/_ICP1_/_CLKO)_22") (pintype "bidirectional"))
    )
  )
)
